# mosfet-pcb.net
KiCad netlist of a schematic drawn in EasyEDA Pro
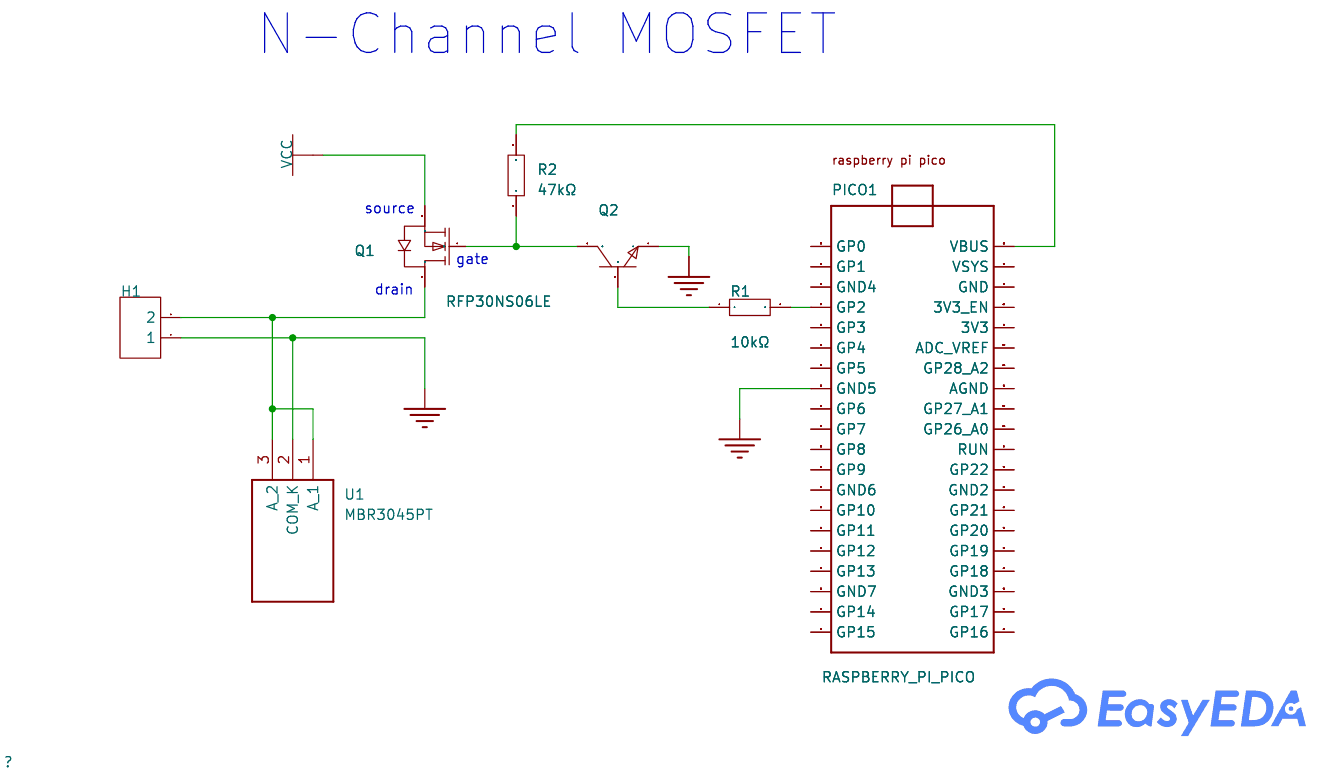
[diagram p0: schematic sheet]

(export (version "E")
  (design (tool "Eeschema 10.0.6"))
  (components
    (comp (ref "H1")
      (value "~")
      (footprint "easyedapro:HDR-TH_2P-P2.54-V-F")
      (libsource (lib "easyedapro") (part "Header-Female-2.54_1x2"))
    )
    (comp (ref "PICO1")
      (value "RASPBERRY_PI_PICO")
      (footprint "easyedapro:RASPBERRY_PI_PICO")
      (libsource (lib "easyedapro") (part "RASPBERRY_PI_PICO"))
    )
    (comp (ref "Q1")
      (value "RFP30NS06LE")
      (footprint "easyedapro:TO-252-2_L6.6-W6.1-P4.57-LS9.9-BR-CW")
      (fields (field (name "Manufacturer Part") "UMW30N06") (field (name "Manufacturer") "UMW(友台半导体)"))
      (libsource (lib "easyedapro") (part "UMW30N06"))
    )
    (comp (ref "Q2")
      (value "~")
      (footprint "easyedapro:S8050_TO_92")
      (fields (field (name "Manufacturer") "ST(先科)"))
      (libsource (lib "easyedapro") (part "S8050_TO_NPN"))
    )
    (comp (ref "R1")
      (value "10kΩ")
      (footprint "easyedapro:R0603")
      (fields
        (field (name "Manufacturer Part") "TR0805B10K0P0525Z")
        (field (name "Manufacturer") "EVER OHMS(天二科技)")
      )
      (libsource (lib "easyedapro") (part "电阻"))
    )
    (comp (ref "R2")
      (value "47kΩ")
      (footprint "easyedapro:R0603")
      (fields (field (name "Manufacturer Part") "RC0805JR-0747KL") (field (name "Manufacturer") "YAGEO(国巨)"))
      (libsource (lib "easyedapro") (part "电阻"))
    )
    (comp (ref "U1")
      (value "MBR3045PT")
      (footprint "easyedapro:TO545P505X1600X2560-3P")
      (libsource (lib "easyedapro") (part "MBR3045PT"))
    )
  )
  (nets
    (net (code "1") (name "GND") (class "Default")
      (node (ref "H1") (pin "1") (pinfunction "1_1") (pintype "input"))
      (node (ref "PICO1") (pin "GND5") (pinfunction "GND5_GND5") (pintype "bidirectional"))
      (node (ref "Q2") (pin "1") (pinfunction "E_1") (pintype "unspecified"))
      (node (ref "U1") (pin "2") (pinfunction "COM_K_2") (pintype "bidirectional"))
    )
    (net (code "2") (name "Net-(PICO1-PadGP2)") (class "Default")
      (node (ref "PICO1") (pin "GP2") (pinfunction "GP2_GP2") (pintype "bidirectional"))
      (node (ref "R1") (pin "2") (pinfunction "2_2") (pintype "input"))
    )
    (net (code "3") (name "Net-(PICO1-PadVBUS)") (class "Default")
      (node (ref "PICO1") (pin "VBUS") (pinfunction "VBUS_VBUS") (pintype "bidirectional"))
      (node (ref "R2") (pin "2") (pinfunction "2_2") (pintype "input"))
    )
    (net (code "4") (name "Net-(Q1-D)") (class "Default")
      (node (ref "H1") (pin "2") (pinfunction "2_2") (pintype "input"))
      (node (ref "Q1") (pin "2") (pinfunction "D_2") (pintype "input"))
      (node (ref "U1") (pin "1") (pinfunction "A_1_1") (pintype "bidirectional"))
      (node (ref "U1") (pin "3") (pinfunction "A_2_3") (pintype "bidirectional"))
    )
    (net (code "5") (name "Net-(Q1-G)") (class "Default")
      (node (ref "Q1") (pin "1") (pinfunction "G_1") (pintype "input"))
      (node (ref "Q2") (pin "3") (pinfunction "C_3") (pintype "unspecified"))
      (node (ref "R2") (pin "1") (pinfunction "1_1") (pintype "input"))
    )
    (net (code "6") (name "Net-(Q2-B)") (class "Default")
      (node (ref "Q2") (pin "2") (pinfunction "B_2") (pintype "unspecified"))
      (node (ref "R1") (pin "1") (pinfunction "1_1") (pintype "input"))
    )
    (net (code "7") (name "VCC") (class "Default")
      (node (ref "Q1") (pin "3") (pinfunction "S_3") (pintype "input"))
    )
    (net (code "8") (name "unconnected-(PICO1-Pad3V3)") (class "Default")
      (node (ref "PICO1") (pin "3V3") (pinfunction "3V3_3V3") (pintype "bidirectional"))
    )
    (net (code "9") (name "unconnected-(PICO1-Pad3V3_EN)") (class "Default")
      (node (ref "PICO1") (pin "3V3_EN") (pinfunction "3V3_EN_3V3_EN") (pintype "bidirectional"))
    )
    (net (code "10") (name "unconnected-(PICO1-PadADC_VREF)") (class "Default")
      (node (ref "PICO1") (pin "ADC_VREF") (pinfunction "ADC_VREF_ADC_VREF") (pintype "bidirectional"))
    )
    (net (code "11") (name "unconnected-(PICO1-PadAGND)") (class "Default")
      (node (ref "PICO1") (pin "AGND") (pinfunction "AGND_AGND") (pintype "bidirectional"))
    )
    (net (code "12") (name "unconnected-(PICO1-PadGND)") (class "Default")
      (node (ref "PICO1") (pin "GND") (pinfunction "GND_GND") (pintype "bidirectional"))
    )
    (net (code "13") (name "unconnected-(PICO1-PadGND2)") (class "Default")
      (node (ref "PICO1") (pin "GND2") (pinfunction "GND2_GND2") (pintype "bidirectional"))
    )
    (net (code "14") (name "unconnected-(PICO1-PadGND3)") (class "Default")
      (node (ref "PICO1") (pin "GND3") (pinfunction "GND3_GND3") (pintype "bidirectional"))
    )
    (net (code "15") (name "unconnected-(PICO1-PadGND4)") (class "Default")
      (node (ref "PICO1") (pin "GND4") (pinfunction "GND4_GND4") (pintype "bidirectional"))
    )
    (net (code "16") (name "unconnected-(PICO1-PadGND6)") (class "Default")
      (node (ref "PICO1") (pin "GND6") (pinfunction "GND6_GND6") (pintype "bidirectional"))
    )
    (net (code "17") (name "unconnected-(PICO1-PadGND7)") (class "Default")
      (node (ref "PICO1") (pin "GND7") (pinfunction "GND7_GND7") (pintype "bidirectional"))
    )
    (net (code "18") (name "unconnected-(PICO1-PadGP0)") (class "Default")
      (node (ref "PICO1") (pin "GP0") (pinfunction "GP0_GP0") (pintype "bidirectional"))
    )
    (net (code "19") (name "unconnected-(PICO1-PadGP1)") (class "Default")
      (node (ref "PICO1") (pin "GP1") (pinfunction "GP1_GP1") (pintype "bidirectional"))
    )
    (net (code "20") (name "unconnected-(PICO1-PadGP3)") (class "Default")
      (node (ref "PICO1") (pin "GP3") (pinfunction "GP3_GP3") (pintype "bidirectional"))
    )
    (net (code "21") (name "unconnected-(PICO1-PadGP4)") (class "Default")
      (node (ref "PICO1") (pin "GP4") (pinfunction "GP4_GP4") (pintype "bidirectional"))
    )
    (net (code "22") (name "unconnected-(PICO1-PadGP5)") (class "Default")
      (node (ref "PICO1") (pin "GP5") (pinfunction "GP5_GP5") (pintype "bidirectional"))
    )
    (net (code "23") (name "unconnected-(PICO1-PadGP6)") (class "Default")
      (node (ref "PICO1") (pin "GP6") (pinfunction "GP6_GP6") (pintype "bidirectional"))
    )
    (net (code "24") (name "unconnected-(PICO1-PadGP7)") (class "Default")
      (node (ref "PICO1") (pin "GP7") (pinfunction "GP7_GP7") (pintype "bidirectional"))
    )
    (net (code "25") (name "unconnected-(PICO1-PadGP8)") (class "Default")
      (node (ref "PICO1") (pin "GP8") (pinfunction "GP8_GP8") (pintype "bidirectional"))
    )
    (net (code "26") (name "unconnected-(PICO1-PadGP9)") (class "Default")
      (node (ref "PICO1") (pin "GP9") (pinfunction "GP9_GP9") (pintype "bidirectional"))
    )
    (net (code "27") (name "unconnected-(PICO1-PadGP10)") (class "Default")
      (node (ref "PICO1") (pin "GP10") (pinfunction "GP10_GP10") (pintype "bidirectional"))
    )
    (net (code "28") (name "unconnected-(PICO1-PadGP11)") (class "Default")
      (node (ref "PICO1") (pin "GP11") (pinfunction "GP11_GP11") (pintype "bidirectional"))
    )
    (net (code "29") (name "unconnected-(PICO1-PadGP12)") (class "Default")
      (node (ref "PICO1") (pin "GP12") (pinfunction "GP12_GP12") (pintype "bidirectional"))
    )
    (net (code "30") (name "unconnected-(PICO1-PadGP13)") (class "Default")
      (node (ref "PICO1") (pin "GP13") (pinfunction "GP13_GP13") (pintype "bidirectional"))
    )
    (net (code "31") (name "unconnected-(PICO1-PadGP14)") (class "Default")
      (node (ref "PICO1") (pin "GP14") (pinfunction "GP14_GP14") (pintype "bidirectional"))
    )
    (net (code "32") (name "unconnected-(PICO1-PadGP15)") (class "Default")
      (node (ref "PICO1") (pin "GP15") (pinfunction "GP15_GP15") (pintype "bidirectional"))
    )
    (net (code "33") (name "unconnected-(PICO1-PadGP16)") (class "Default")
      (node (ref "PICO1") (pin "GP16") (pinfunction "GP16_GP16") (pintype "bidirectional"))
    )
    (net (code "34") (name "unconnected-(PICO1-PadGP17)") (class "Default")
      (node (ref "PICO1") (pin "GP17") (pinfunction "GP17_GP17") (pintype "bidirectional"))
    )
    (net (code "35") (name "unconnected-(PICO1-PadGP18)") (class "Default")
      (node (ref "PICO1") (pin "GP18") (pinfunction "GP18_GP18") (pintype "bidirectional"))
    )
    (net (code "36") (name "unconnected-(PICO1-PadGP19)") (class "Default")
      (node (ref "PICO1") (pin "GP19") (pinfunction "GP19_GP19") (pintype "bidirectional"))
    )
    (net (code "37") (name "unconnected-(PICO1-PadGP20)") (class "Default")
      (node (ref "PICO1") (pin "GP20") (pinfunction "GP20_GP20") (pintype "bidirectional"))
    )
    (net (code "38") (name "unconnected-(PICO1-PadGP21)") (class "Default")
      (node (ref "PICO1") (pin "GP21") (pinfunction "GP21_GP21") (pintype "bidirectional"))
    )
    (net (code "39") (name "unconnected-(PICO1-PadGP22)") (class "Default")
      (node (ref "PICO1") (pin "GP22") (pinfunction "GP22_GP22") (pintype "bidirectional"))
    )
    (net (code "40") (name "unconnected-(PICO1-PadGP26_A0)") (class "Default")
      (node (ref "PICO1") (pin "GP26_A0") (pinfunction "GP26_A0_GP26_A0") (pintype "bidirectional"))
    )
    (net (code "41") (name "unconnected-(PICO1-PadGP27_A1)") (class "Default")
      (node (ref "PICO1") (pin "GP27_A1") (pinfunction "GP27_A1_GP27_A1") (pintype "bidirectional"))
    )
    (net (code "42") (name "unconnected-(PICO1-PadGP28_A2)") (class "Default")
      (node (ref "PICO1") (pin "GP28_A2") (pinfunction "GP28_A2_GP28_A2") (pintype "bidirectional"))
    )
    (net (code "43") (name "unconnected-(PICO1-PadRUN)") (class "Default")
      (node (ref "PICO1") (pin "RUN") (pinfunction "RUN_RUN") (pintype "bidirectional"))
    )
    (net (code "44") (name "unconnected-(PICO1-PadVSYS)") (class "Default")
      (node (ref "PICO1") (pin "VSYS") (pinfunction "VSYS_VSYS") (pintype "bidirectional"))
    )
  )
)
